# Face_HM1V0.net
KiCad netlist of a schematic drawn in Altium Designer
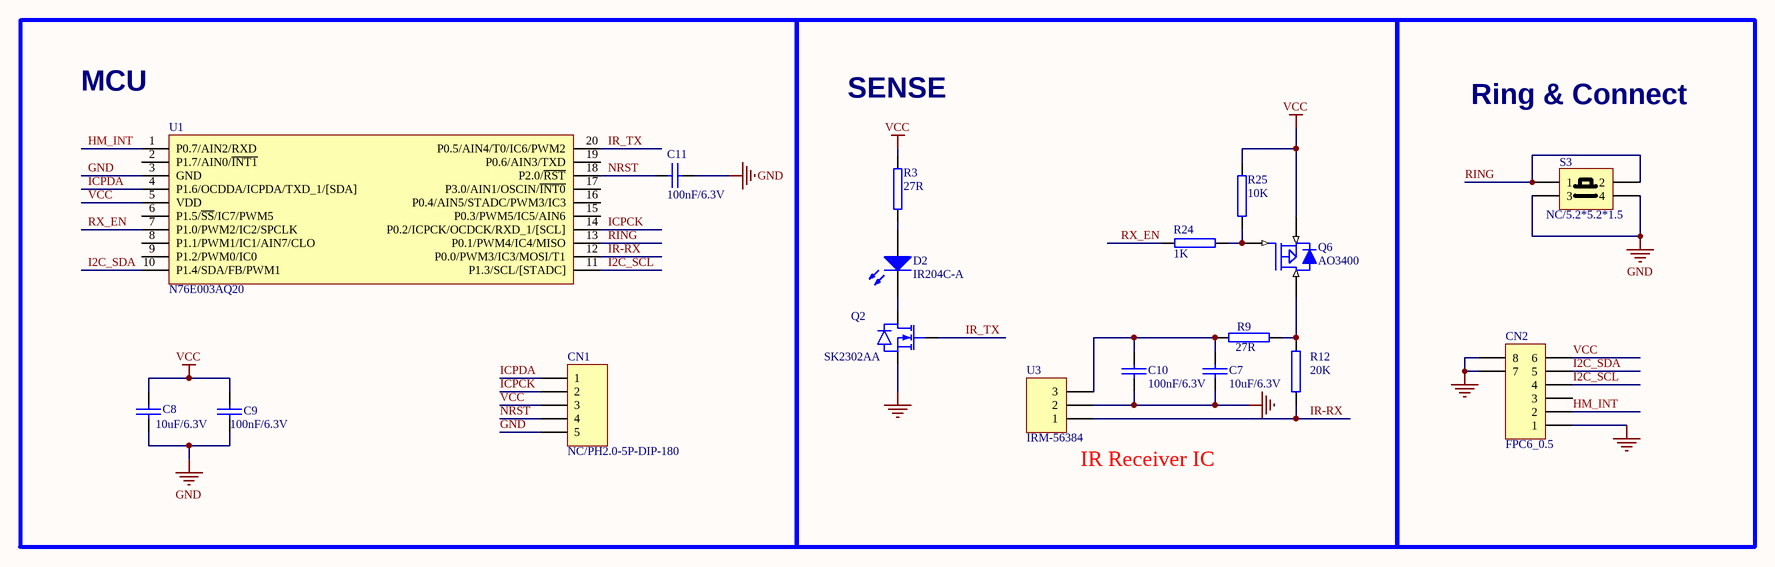
[diagram p0: Face_HM1V0.SchDoc]

(export (version "E")
  (design (tool "Eeschema 10.0.6"))
  (components
    (comp (ref "C7")
      (value "10uf ±10% 6.3V X7R 0603 ROSH ROHS")
      (footprint "C0603")
      (description "10uf ±10% 6.3V X7R 0603 ROHS")
      (fields (field (name "ALTIUM_UNNAMED_1") "10uF/6.3V"))
      (libsource (lib "*") (part "CAP"))
    )
    (comp (ref "C8")
      (value "10uf ±10% 6.3V X7R 0603 ROSH ROHS")
      (footprint "C0603")
      (description "10uf ±10% 6.3V X7R 0603 ROHS")
      (fields (field (name "ALTIUM_UNNAMED_1") "10uF/6.3V"))
      (libsource (lib "*") (part "CAP"))
    )
    (comp (ref "C9")
      (value "100nF/6.3V 10% 0402 X7R ROHS")
      (footprint "C0402")
      (fields (field (name "ALTIUM_UNNAMED_1") "100nF/6.3V"))
      (libsource (lib "*") (part "CAP"))
    )
    (comp (ref "C10")
      (value "100nF/6.3V 10% 0402 X7R ROHS")
      (footprint "C0402")
      (fields (field (name "ALTIUM_UNNAMED_1") "100nF/6.3V"))
      (libsource (lib "*") (part "CAP"))
    )
    (comp (ref "C11")
      (value "100nF/6.3V 10% 0402 X7R ROHS")
      (footprint "C0402")
      (fields (field (name "ALTIUM_UNNAMED_1") "100nF/6.3V"))
      (libsource (lib "*") (part "CAP"))
    )
    (comp (ref "CN1")
      (value "NC/Header")
      (footprint "HD2.0_5P")
      (description "Header ,5pin")
      (fields (field (name "NAME1") "NC/PH2.0-5P-DIP-180"))
      (libsource (lib "LM") (part "Header5"))
    )
    (comp (ref "CN2")
      (value "FPC6_0.5")
      (footprint "FPC0.5_6P_STRAIGHT")
      (libsource (lib "S6X_1V0") (part "Header 6"))
    )
    (comp (ref "D2")
      (value "IR204C-A")
      (footprint "LD5.0_1 - duplicate")
      (fields (field (name "ALTIUM_UNNAMED_1") "IR204C-A"))
      (libsource (lib "FLMain1v10") (part "LED0"))
    )
    (comp (ref "Q2")
      (value "SK2302AA")
      (footprint "SOT-23-3")
      (libsource (lib "Miscellaneous Devices") (part "MOSFET-N"))
    )
    (comp (ref "Q6") (value "AO3400") (footprint "SOT-23-3") (libsource (lib "*") (part "IRLML6402")))
    (comp (ref "R3")
      (value "27R 5% 1/16W 0402 ROHS")
      (footprint "R0402")
      (fields (field (name "ALTIUM_UNNAMED_1") "27R"))
      (libsource (lib "*") (part "RES2"))
    )
    (comp (ref "R9")
      (value "27R 5% 1/16W 0402 ROHS")
      (footprint "R0402")
      (fields (field (name "ALTIUM_UNNAMED_1") "27R"))
      (libsource (lib "*") (part "RES2"))
    )
    (comp (ref "R12")
      (value "20K 5% 1/16W 0402 ROHS")
      (footprint "R0402")
      (fields (field (name "ALTIUM_UNNAMED_1") "20K"))
      (libsource (lib "*") (part "RES2"))
    )
    (comp (ref "R24")
      (value "1K 5% 1/16W 0402 ROHS")
      (footprint "R0402")
      (fields (field (name "ALTIUM_UNNAMED_1") "1K"))
      (libsource (lib "*") (part "RES2"))
    )
    (comp (ref "R25")
      (value "10K 5% 1/16W 0402 ROHS")
      (footprint "R0402")
      (fields (field (name "ALTIUM_UNNAMED_1") "10K"))
      (libsource (lib "*") (part "RES2"))
    )
    (comp (ref "S3")
      (value "NC/5.2*5.2*1.5")
      (footprint "5.2X5.2X1.5 TACT SWITCH")
      (description "Tactile Switch KEY6x6")
      (fields (field (name "PUBLISHER") "Altium Limited"))
      (libsource (lib "LM") (part "Tactile Switch KEY6x6"))
    )
    (comp (ref "U1")
      (value "N76E003AQ20(QFN20)")
      (footprint "QFN20_3*3mm")
      (fields (field (name "ALTIUM_UNNAMED_1") "N76E003AQ20"))
      (libsource (lib "LM") (part "N76E003AQ20"))
    )
    (comp (ref "U3")
      (value "IRM-56384")
      (footprint "IRM-3638 - duplicate")
      (fields (field (name "ALTIUM_UNNAMED_1") "IRM-56384"))
      (libsource (lib "Miscellaneous Connectors") (part "Header 3"))
    )
  )
  (nets
    (net (code "1") (name "/HM_INT") (class "Default")
      (node (ref "CN2") (pin "2") (pinfunction "2_2") (pintype "passive"))
      (node (ref "U1") (pin "1") (pinfunction "P0.7/AIN2/RXD_1") (pintype "passive"))
    )
    (net (code "2") (name "/I2C_SCL") (class "Default")
      (node (ref "CN2") (pin "4") (pinfunction "4_4") (pintype "passive"))
      (node (ref "U1") (pin "11") (pinfunction "P1.3/SCL/[STADC]_11") (pintype "passive"))
    )
    (net (code "3") (name "/I2C_SDA") (class "Default")
      (node (ref "CN2") (pin "5") (pinfunction "5_5") (pintype "passive"))
      (node (ref "U1") (pin "10") (pinfunction "P1.4/SDA/FB/PWM1_10") (pintype "passive"))
    )
    (net (code "4") (name "/ICPCK") (class "Default")
      (node (ref "CN1") (pin "2") (pinfunction "2_2") (pintype "passive"))
      (node (ref "U1") (pin "14") (pinfunction "P0.2/ICPCK/OCDCK/RXD_1/[SCL]_14") (pintype "passive"))
    )
    (net (code "5") (name "/ICPDA") (class "Default")
      (node (ref "CN1") (pin "1") (pinfunction "1_1") (pintype "passive"))
      (node (ref "U1") (pin "4") (pinfunction "P1.6/OCDDA/ICPDA/TXD_1/[SDA]_4") (pintype "passive"))
    )
    (net (code "6") (name "/IR-RX") (class "Default")
      (node (ref "R12") (pin "2") (pinfunction "2_2") (pintype "passive"))
      (node (ref "U1") (pin "12") (pinfunction "P0.0/PWM3/IC3/MOSI/T1_12") (pintype "passive"))
      (node (ref "U3") (pin "1") (pinfunction "1_1") (pintype "passive"))
    )
    (net (code "7") (name "/IR_TX") (class "Default")
      (node (ref "Q2") (pin "1") (pinfunction "G_1") (pintype "passive"))
      (node (ref "U1") (pin "20") (pinfunction "P0.5/AIN4/T0/IC6/PWM2_20") (pintype "passive"))
    )
    (net (code "8") (name "/NRST") (class "Default")
      (node (ref "C11") (pin "1") (pinfunction "1_1") (pintype "passive"))
      (node (ref "CN1") (pin "4") (pinfunction "4_4") (pintype "passive"))
      (node (ref "U1") (pin "18") (pinfunction "P2.0/~{RST}_18") (pintype "passive"))
    )
    (net (code "9") (name "/RING") (class "Default")
      (node (ref "S3") (pin "1") (pinfunction "1_1") (pintype "passive"))
      (node (ref "S3") (pin "2") (pinfunction "2_2") (pintype "passive"))
      (node (ref "U1") (pin "13") (pinfunction "P0.1/PWM4/IC4/MISO_13") (pintype "passive"))
    )
    (net (code "10") (name "/RX_EN") (class "Default")
      (node (ref "R24") (pin "1") (pinfunction "1_1") (pintype "passive"))
      (node (ref "U1") (pin "7") (pinfunction "P1.0/PWM2/IC2/SPCLK_7") (pintype "passive"))
    )
    (net (code "11") (name "GND") (class "Default")
      (node (ref "C10") (pin "2") (pinfunction "2_2") (pintype "passive"))
      (node (ref "C11") (pin "2") (pinfunction "2_2") (pintype "passive"))
      (node (ref "C7") (pin "2") (pinfunction "2_2") (pintype "passive"))
      (node (ref "C8") (pin "2") (pinfunction "2_2") (pintype "passive"))
      (node (ref "C9") (pin "2") (pinfunction "2_2") (pintype "passive"))
      (node (ref "CN1") (pin "5") (pinfunction "5_5") (pintype "passive"))
      (node (ref "CN2") (pin "1") (pinfunction "1_1") (pintype "passive"))
      (node (ref "CN2") (pin "7") (pinfunction "7_7") (pintype "passive"))
      (node (ref "CN2") (pin "8") (pinfunction "8_8") (pintype "passive"))
      (node (ref "Q2") (pin "2") (pinfunction "S_2") (pintype "passive"))
      (node (ref "S3") (pin "3") (pinfunction "3_3") (pintype "passive"))
      (node (ref "S3") (pin "4") (pinfunction "4_4") (pintype "passive"))
      (node (ref "U1") (pin "3") (pinfunction "GND_3") (pintype "passive"))
      (node (ref "U3") (pin "2") (pinfunction "2_2") (pintype "passive"))
    )
    (net (code "12") (name "Net-(C10-Pad1)") (class "Default")
      (node (ref "C10") (pin "1") (pinfunction "1_1") (pintype "passive"))
      (node (ref "C7") (pin "1") (pinfunction "1_1") (pintype "passive"))
      (node (ref "R9") (pin "2") (pinfunction "2_2") (pintype "passive"))
      (node (ref "U3") (pin "3") (pinfunction "3_3") (pintype "passive"))
    )
    (net (code "13") (name "Net-(D2-1)") (class "Default")
      (node (ref "D2") (pin "A") (pinfunction "1_A") (pintype "passive"))
      (node (ref "R3") (pin "2") (pinfunction "2_2") (pintype "passive"))
    )
    (net (code "14") (name "Net-(D2-2)") (class "Default")
      (node (ref "D2") (pin "K") (pinfunction "2_K") (pintype "passive"))
      (node (ref "Q2") (pin "3") (pinfunction "D_3") (pintype "passive"))
    )
    (net (code "15") (name "Net-(Q6-D)") (class "Default")
      (node (ref "Q6") (pin "3") (pinfunction "D_3") (pintype "input"))
      (node (ref "R12") (pin "1") (pinfunction "1_1") (pintype "passive"))
      (node (ref "R9") (pin "1") (pinfunction "1_1") (pintype "passive"))
    )
    (net (code "16") (name "Net-(Q6-G)") (class "Default")
      (node (ref "Q6") (pin "1") (pinfunction "G_1") (pintype "input"))
      (node (ref "R24") (pin "2") (pinfunction "2_2") (pintype "passive"))
      (node (ref "R25") (pin "1") (pinfunction "1_1") (pintype "passive"))
    )
    (net (code "17") (name "VCC") (class "Default")
      (node (ref "C8") (pin "1") (pinfunction "1_1") (pintype "passive"))
      (node (ref "C9") (pin "1") (pinfunction "1_1") (pintype "passive"))
      (node (ref "CN1") (pin "3") (pinfunction "3_3") (pintype "passive"))
      (node (ref "CN2") (pin "6") (pinfunction "6_6") (pintype "passive"))
      (node (ref "Q6") (pin "2") (pinfunction "S_2") (pintype "input"))
      (node (ref "R25") (pin "2") (pinfunction "2_2") (pintype "passive"))
      (node (ref "R3") (pin "1") (pinfunction "1_1") (pintype "passive"))
      (node (ref "U1") (pin "5") (pinfunction "VDD_5") (pintype "passive"))
    )
    (net (code "18") (name "unconnected-(CN2-Pad3)") (class "Default")
      (node (ref "CN2") (pin "3") (pinfunction "3_3") (pintype "passive"))
    )
    (net (code "19") (name "unconnected-(U1-P0.3{slash}PWM5{slash}IC5{slash}AIN6-Pad15)") (class "Default")
      (node (ref "U1") (pin "15") (pinfunction "P0.3/PWM5/IC5/AIN6_15") (pintype "passive"))
    )
    (net (code "20") (name "unconnected-(U1-P0.4{slash}AIN5{slash}STADC{slash}PWM3{slash}IC3-Pad16)") (class "Default")
      (node (ref "U1") (pin "16") (pinfunction "P0.4/AIN5/STADC/PWM3/IC3_16") (pintype "passive"))
    )
    (net (code "21") (name "unconnected-(U1-P0.6{slash}AIN3{slash}TXD-Pad19)") (class "Default")
      (node (ref "U1") (pin "19") (pinfunction "P0.6/AIN3/TXD_19") (pintype "passive"))
    )
    (net (code "22") (name "unconnected-(U1-P1.1{slash}PWM1{slash}IC1{slash}AIN7{slash}CLO-Pad8)") (class "Default")
      (node (ref "U1") (pin "8") (pinfunction "P1.1/PWM1/IC1/AIN7/CLO_8") (pintype "passive"))
    )
    (net (code "23") (name "unconnected-(U1-P1.2{slash}PWM0{slash}IC0-Pad9)") (class "Default")
      (node (ref "U1") (pin "9") (pinfunction "P1.2/PWM0/IC0_9") (pintype "passive"))
    )
    (net (code "24") (name "unconnected-(U1-P1.5{slash}~{SS}{slash}IC7{slash}PWM5-Pad6)") (class "Default")
      (node (ref "U1") (pin "6") (pinfunction "P1.5/~{SS}/IC7/PWM5_6") (pintype "passive"))
    )
    (net (code "25") (name "unconnected-(U1-P1.7{slash}AIN0{slash}~{INT1}-Pad2)") (class "Default")
      (node (ref "U1") (pin "2") (pinfunction "P1.7/AIN0/~{INT1}_2") (pintype "passive"))
    )
    (net (code "26") (name "unconnected-(U1-P3.0{slash}AIN1{slash}OSCIN{slash}~{INT0}-Pad17)") (class "Default")
      (node (ref "U1") (pin "17") (pinfunction "P3.0/AIN1/OSCIN/~{INT0}_17") (pintype "passive"))
    )
  )
)
